# design.net
KiCad netlist of a schematic drawn in EasyEDA
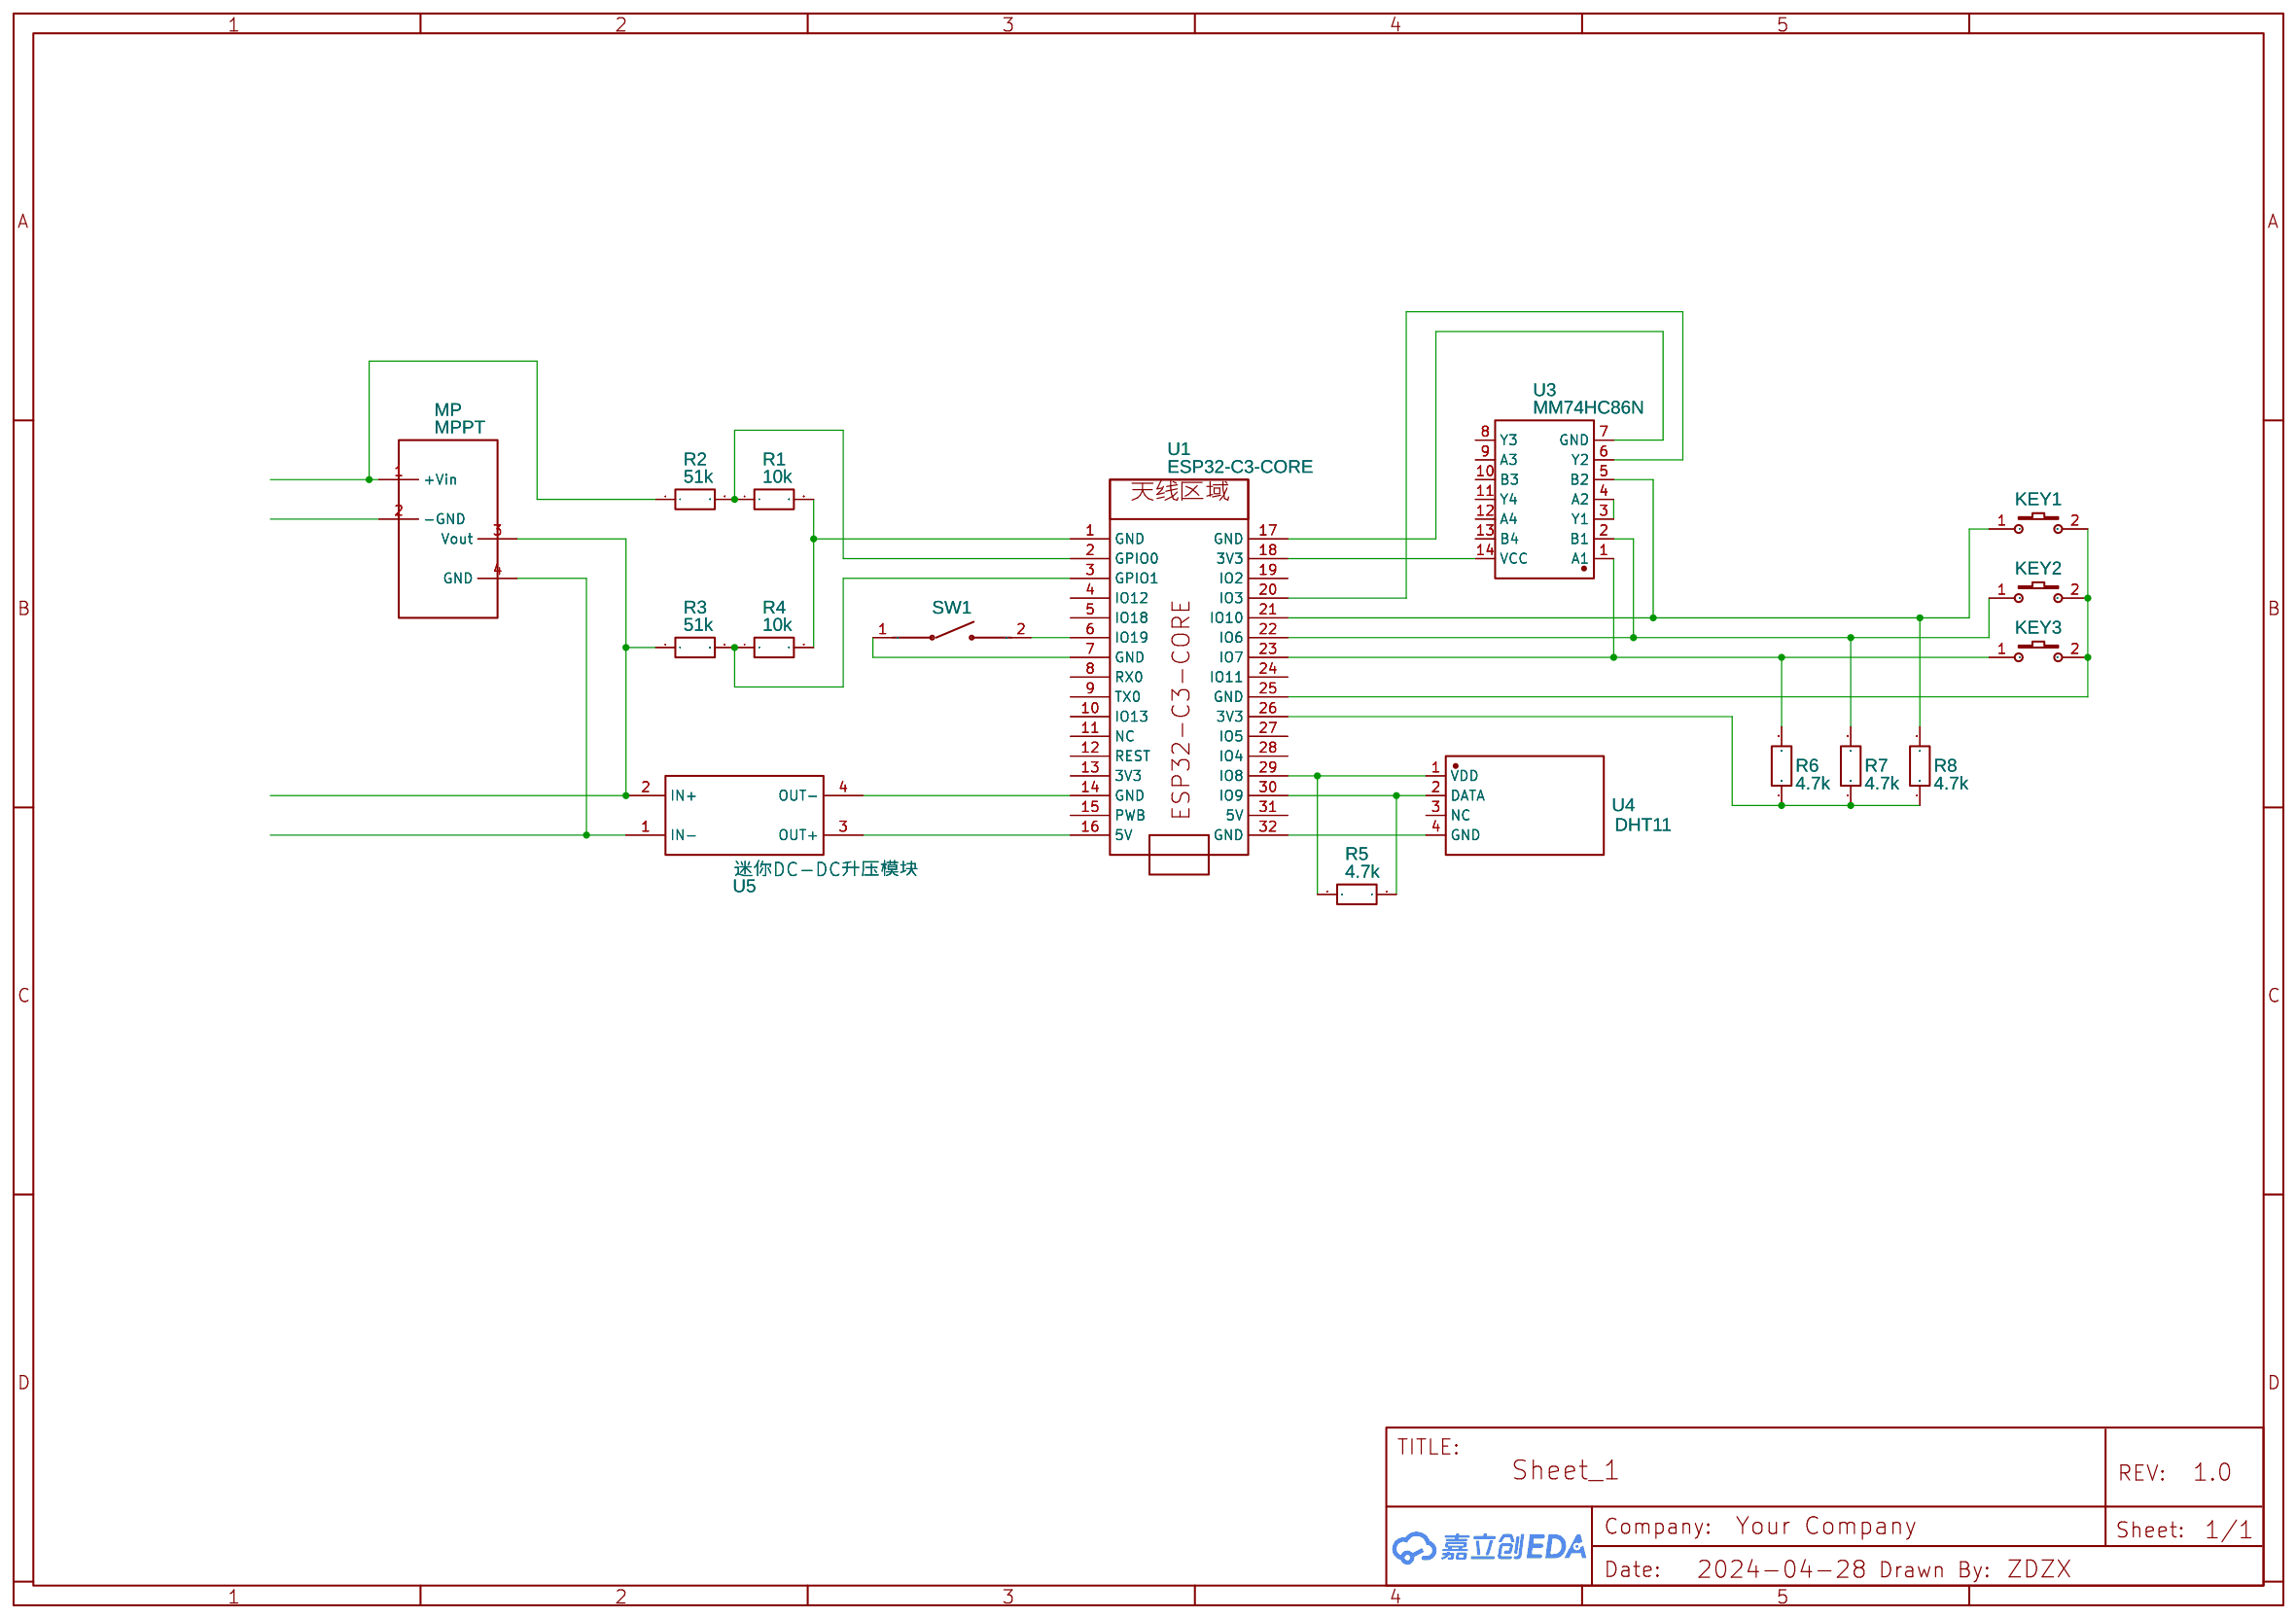
[diagram p0: schematic sheet]

(export (version "E")
  (design (tool "Eeschema 10.0.6"))
  (components
    (comp (ref "KEY1")
      (value "K2-3.6×6.1_SMD")
      (fields (field (name "Manufacturer Part") "K2-1107ST-A4SW-06"))
      (libsource (lib "") (part "K2-3.6×6.1_SMD"))
    )
    (comp (ref "KEY2")
      (value "K2-3.6×6.1_SMD")
      (fields (field (name "Manufacturer Part") "K2-1107ST-A4SW-06"))
      (libsource (lib "") (part "K2-3.6×6.1_SMD"))
    )
    (comp (ref "KEY3")
      (value "K2-3.6×6.1_SMD")
      (fields (field (name "Manufacturer Part") "K2-1107ST-A4SW-06"))
      (libsource (lib "") (part "K2-3.6×6.1_SMD"))
    )
    (comp (ref "MP") (value "MPPT") (libsource (lib "") (part "MPPT")))
    (comp (ref "R1") (value "10k") (libsource (lib "") (part "R_0603_EU")))
    (comp (ref "R2") (value "51k") (libsource (lib "") (part "R_0603_EU")))
    (comp (ref "R3") (value "51k") (libsource (lib "") (part "R_0603_EU")))
    (comp (ref "R4") (value "10k") (libsource (lib "") (part "R_0603_EU")))
    (comp (ref "R5") (value "4.7k") (libsource (lib "") (part "R_0603_EU")))
    (comp (ref "R6") (value "4.7k") (libsource (lib "") (part "R_0603_EU_1")))
    (comp (ref "R7") (value "4.7k") (libsource (lib "") (part "R_0603_EU_1")))
    (comp (ref "R8") (value "4.7k") (libsource (lib "") (part "R_0603_EU_1")))
    (comp (ref "SW1")
      (value "1-1571076-0")
      (fields (field (name "Manufacturer") "TE Connectivity(泰科电子)"))
      (libsource (lib "") (part "1-1571076-0"))
    )
    (comp (ref "U1") (value "ESP32-C3-CORE") (libsource (lib "") (part "ESP32-C3-CORE")))
    (comp (ref "U3")
      (value "MM74HC86N")
      (fields (field (name "Manufacturer") "onsemi(安森美)"))
      (libsource (lib "") (part "MM74HC86N"))
    )
    (comp (ref "U4")
      (value "DHT11")
      (fields (field (name "Manufacturer") "广州奥松"))
      (libsource (lib "") (part "DHT11"))
    )
    (comp (ref "U5") (value "迷你DC-DC升压模块") (libsource (lib "") (part "迷你DC-DC升压模块")))
  )
  (nets
    (net (code "1") (name "Net-(KEY1-Pad2)") (class "Default")
      (node (ref "KEY1") (pin "2") (pinfunction "2_2") (pintype "unspecified"))
      (node (ref "KEY2") (pin "2") (pinfunction "2_2") (pintype "unspecified"))
      (node (ref "KEY3") (pin "2") (pinfunction "2_2") (pintype "unspecified"))
      (node (ref "U1") (pin "25") (pinfunction "GND_25") (pintype "unspecified"))
    )
    (net (code "2") (name "Net-(MP-+Vin)") (class "Default")
      (node (ref "MP") (pin "1") (pinfunction "+Vin_1") (pintype "unspecified"))
      (node (ref "R2") (pin "1") (pinfunction "1_1") (pintype "unspecified"))
    )
    (net (code "3") (name "Net-(MP-GND)") (class "Default")
      (node (ref "MP") (pin "4") (pinfunction "GND_4") (pintype "unspecified"))
      (node (ref "U5") (pin "1") (pinfunction "IN-_1") (pintype "unspecified"))
    )
    (net (code "4") (name "Net-(MP-Vout)") (class "Default")
      (node (ref "MP") (pin "3") (pinfunction "Vout_3") (pintype "unspecified"))
      (node (ref "R3") (pin "1") (pinfunction "1_1") (pintype "unspecified"))
      (node (ref "U5") (pin "2") (pinfunction "IN+_2") (pintype "unspecified"))
    )
    (net (code "5") (name "Net-(R1-Pad2)") (class "Default")
      (node (ref "R1") (pin "2") (pinfunction "2_2") (pintype "unspecified"))
      (node (ref "R4") (pin "2") (pinfunction "2_2") (pintype "unspecified"))
      (node (ref "U1") (pin "1") (pinfunction "GND_1") (pintype "unspecified"))
    )
    (net (code "6") (name "Net-(R6-Pad1)") (class "Default")
      (node (ref "R6") (pin "1") (pinfunction "1_1") (pintype "unspecified"))
      (node (ref "R7") (pin "1") (pinfunction "1_1") (pintype "unspecified"))
      (node (ref "R8") (pin "1") (pinfunction "1_1") (pintype "unspecified"))
      (node (ref "U1") (pin "26") (pinfunction "3V3_26") (pintype "unspecified"))
    )
    (net (code "7") (name "Net-(SW1-Pad1)") (class "Default")
      (node (ref "SW1") (pin "1") (pinfunction "1_1") (pintype "unspecified"))
      (node (ref "U1") (pin "7") (pinfunction "GND_7") (pintype "unspecified"))
    )
    (net (code "8") (name "Net-(U1-GPIO0)") (class "Default")
      (node (ref "R1") (pin "1") (pinfunction "1_1") (pintype "unspecified"))
      (node (ref "R2") (pin "2") (pinfunction "2_2") (pintype "unspecified"))
      (node (ref "U1") (pin "2") (pinfunction "GPIO0_2") (pintype "unspecified"))
    )
    (net (code "9") (name "Net-(U1-GPIO1)") (class "Default")
      (node (ref "R3") (pin "2") (pinfunction "2_2") (pintype "unspecified"))
      (node (ref "R4") (pin "1") (pinfunction "1_1") (pintype "unspecified"))
      (node (ref "U1") (pin "3") (pinfunction "GPIO1_3") (pintype "unspecified"))
    )
    (net (code "10") (name "Net-(U1-IO3)") (class "Default")
      (node (ref "U1") (pin "20") (pinfunction "IO3_20") (pintype "unspecified"))
      (node (ref "U3") (pin "6") (pinfunction "Y2_6") (pintype "unspecified"))
    )
    (net (code "11") (name "Net-(U1-IO6)") (class "Default")
      (node (ref "KEY2") (pin "1") (pinfunction "1_1") (pintype "unspecified"))
      (node (ref "R7") (pin "2") (pinfunction "2_2") (pintype "unspecified"))
      (node (ref "U1") (pin "22") (pinfunction "IO6_22") (pintype "unspecified"))
      (node (ref "U3") (pin "2") (pinfunction "B1_2") (pintype "unspecified"))
    )
    (net (code "12") (name "Net-(U1-IO7)") (class "Default")
      (node (ref "KEY3") (pin "1") (pinfunction "1_1") (pintype "unspecified"))
      (node (ref "R6") (pin "2") (pinfunction "2_2") (pintype "unspecified"))
      (node (ref "U1") (pin "23") (pinfunction "IO7_23") (pintype "unspecified"))
      (node (ref "U3") (pin "1") (pinfunction "A1_1") (pintype "unspecified"))
    )
    (net (code "13") (name "Net-(U1-IO8)") (class "Default")
      (node (ref "R5") (pin "1") (pinfunction "1_1") (pintype "unspecified"))
      (node (ref "U1") (pin "29") (pinfunction "IO8_29") (pintype "unspecified"))
      (node (ref "U4") (pin "1") (pinfunction "VDD_1") (pintype "unspecified"))
    )
    (net (code "14") (name "Net-(U1-IO9)") (class "Default")
      (node (ref "R5") (pin "2") (pinfunction "2_2") (pintype "unspecified"))
      (node (ref "U1") (pin "30") (pinfunction "IO9_30") (pintype "unspecified"))
      (node (ref "U4") (pin "2") (pinfunction "DATA_2") (pintype "unspecified"))
    )
    (net (code "15") (name "Net-(U1-IO10)") (class "Default")
      (node (ref "KEY1") (pin "1") (pinfunction "1_1") (pintype "unspecified"))
      (node (ref "R8") (pin "2") (pinfunction "2_2") (pintype "unspecified"))
      (node (ref "U1") (pin "21") (pinfunction "IO10_21") (pintype "unspecified"))
      (node (ref "U3") (pin "5") (pinfunction "B2_5") (pintype "unspecified"))
    )
    (net (code "16") (name "Net-(U1-IO19)") (class "Default")
      (node (ref "SW1") (pin "2") (pinfunction "2_2") (pintype "unspecified"))
      (node (ref "U1") (pin "6") (pinfunction "IO19_6") (pintype "unspecified"))
    )
    (net (code "17") (name "Net-(U3-A2)") (class "Default")
      (node (ref "U3") (pin "3") (pinfunction "Y1_3") (pintype "unspecified"))
      (node (ref "U3") (pin "4") (pinfunction "A2_4") (pintype "unspecified"))
    )
    (net (code "18") (name "Net-(U3-GND)") (class "Default")
      (node (ref "U1") (pin "17") (pinfunction "GND_17") (pintype "unspecified"))
      (node (ref "U3") (pin "7") (pinfunction "GND_7") (pintype "unspecified"))
    )
    (net (code "19") (name "Net-(U3-VCC)") (class "Default")
      (node (ref "U1") (pin "18") (pinfunction "3V3_18") (pintype "unspecified"))
      (node (ref "U3") (pin "14") (pinfunction "VCC_14") (pintype "unspecified"))
    )
    (net (code "20") (name "Net-(U4-GND)") (class "Default")
      (node (ref "U1") (pin "32") (pinfunction "GND_32") (pintype "unspecified"))
      (node (ref "U4") (pin "4") (pinfunction "GND_4") (pintype "unspecified"))
    )
    (net (code "21") (name "Net-(U5-OUT+)") (class "Default")
      (node (ref "U1") (pin "16") (pinfunction "5V_16") (pintype "unspecified"))
      (node (ref "U5") (pin "3") (pinfunction "OUT+_3") (pintype "unspecified"))
    )
    (net (code "22") (name "Net-(U5-OUT-)") (class "Default")
      (node (ref "U1") (pin "14") (pinfunction "GND_14") (pintype "unspecified"))
      (node (ref "U5") (pin "4") (pinfunction "OUT-_4") (pintype "unspecified"))
    )
    (net (code "23") (name "unconnected-(MP--GND-Pad2)") (class "Default")
      (node (ref "MP") (pin "2") (pinfunction "-GND_2") (pintype "unspecified"))
    )
    (net (code "24") (name "unconnected-(U1-3V3-Pad13)") (class "Default")
      (node (ref "U1") (pin "13") (pinfunction "3V3_13") (pintype "unspecified"))
    )
    (net (code "25") (name "unconnected-(U1-5V-Pad31)") (class "Default")
      (node (ref "U1") (pin "31") (pinfunction "5V_31") (pintype "unspecified"))
    )
    (net (code "26") (name "unconnected-(U1-IO2-Pad19)") (class "Default")
      (node (ref "U1") (pin "19") (pinfunction "IO2_19") (pintype "unspecified"))
    )
    (net (code "27") (name "unconnected-(U1-IO4-Pad28)") (class "Default")
      (node (ref "U1") (pin "28") (pinfunction "IO4_28") (pintype "unspecified"))
    )
    (net (code "28") (name "unconnected-(U1-IO5-Pad27)") (class "Default")
      (node (ref "U1") (pin "27") (pinfunction "IO5_27") (pintype "unspecified"))
    )
    (net (code "29") (name "unconnected-(U1-IO11-Pad24)") (class "Default")
      (node (ref "U1") (pin "24") (pinfunction "IO11_24") (pintype "unspecified"))
    )
    (net (code "30") (name "unconnected-(U1-IO12-Pad4)") (class "Default")
      (node (ref "U1") (pin "4") (pinfunction "IO12_4") (pintype "unspecified"))
    )
    (net (code "31") (name "unconnected-(U1-IO13-Pad10)") (class "Default")
      (node (ref "U1") (pin "10") (pinfunction "IO13_10") (pintype "unspecified"))
    )
    (net (code "32") (name "unconnected-(U1-IO18-Pad5)") (class "Default")
      (node (ref "U1") (pin "5") (pinfunction "IO18_5") (pintype "unspecified"))
    )
    (net (code "33") (name "unconnected-(U1-NC-Pad11)") (class "Default")
      (node (ref "U1") (pin "11") (pinfunction "NC_11") (pintype "unspecified"))
    )
    (net (code "34") (name "unconnected-(U1-PWB-Pad15)") (class "Default")
      (node (ref "U1") (pin "15") (pinfunction "PWB_15") (pintype "unspecified"))
    )
    (net (code "35") (name "unconnected-(U1-REST-Pad12)") (class "Default")
      (node (ref "U1") (pin "12") (pinfunction "REST_12") (pintype "unspecified"))
    )
    (net (code "36") (name "unconnected-(U1-RX0-Pad8)") (class "Default")
      (node (ref "U1") (pin "8") (pinfunction "RX0_8") (pintype "unspecified"))
    )
    (net (code "37") (name "unconnected-(U1-TX0-Pad9)") (class "Default")
      (node (ref "U1") (pin "9") (pinfunction "TX0_9") (pintype "unspecified"))
    )
    (net (code "38") (name "unconnected-(U3-A3-Pad9)") (class "Default")
      (node (ref "U3") (pin "9") (pinfunction "A3_9") (pintype "unspecified"))
    )
    (net (code "39") (name "unconnected-(U3-A4-Pad12)") (class "Default")
      (node (ref "U3") (pin "12") (pinfunction "A4_12") (pintype "unspecified"))
    )
    (net (code "40") (name "unconnected-(U3-B3-Pad10)") (class "Default")
      (node (ref "U3") (pin "10") (pinfunction "B3_10") (pintype "unspecified"))
    )
    (net (code "41") (name "unconnected-(U3-B4-Pad13)") (class "Default")
      (node (ref "U3") (pin "13") (pinfunction "B4_13") (pintype "unspecified"))
    )
    (net (code "42") (name "unconnected-(U3-Y3-Pad8)") (class "Default")
      (node (ref "U3") (pin "8") (pinfunction "Y3_8") (pintype "unspecified"))
    )
    (net (code "43") (name "unconnected-(U3-Y4-Pad11)") (class "Default")
      (node (ref "U3") (pin "11") (pinfunction "Y4_11") (pintype "unspecified"))
    )
    (net (code "44") (name "unconnected-(U4-NC-Pad3)") (class "Default")
      (node (ref "U4") (pin "3") (pinfunction "NC_3") (pintype "unspecified"))
    )
  )
)
